# SoftCore_SA_P6.net
KiCad netlist of a schematic drawn in Altium Designer
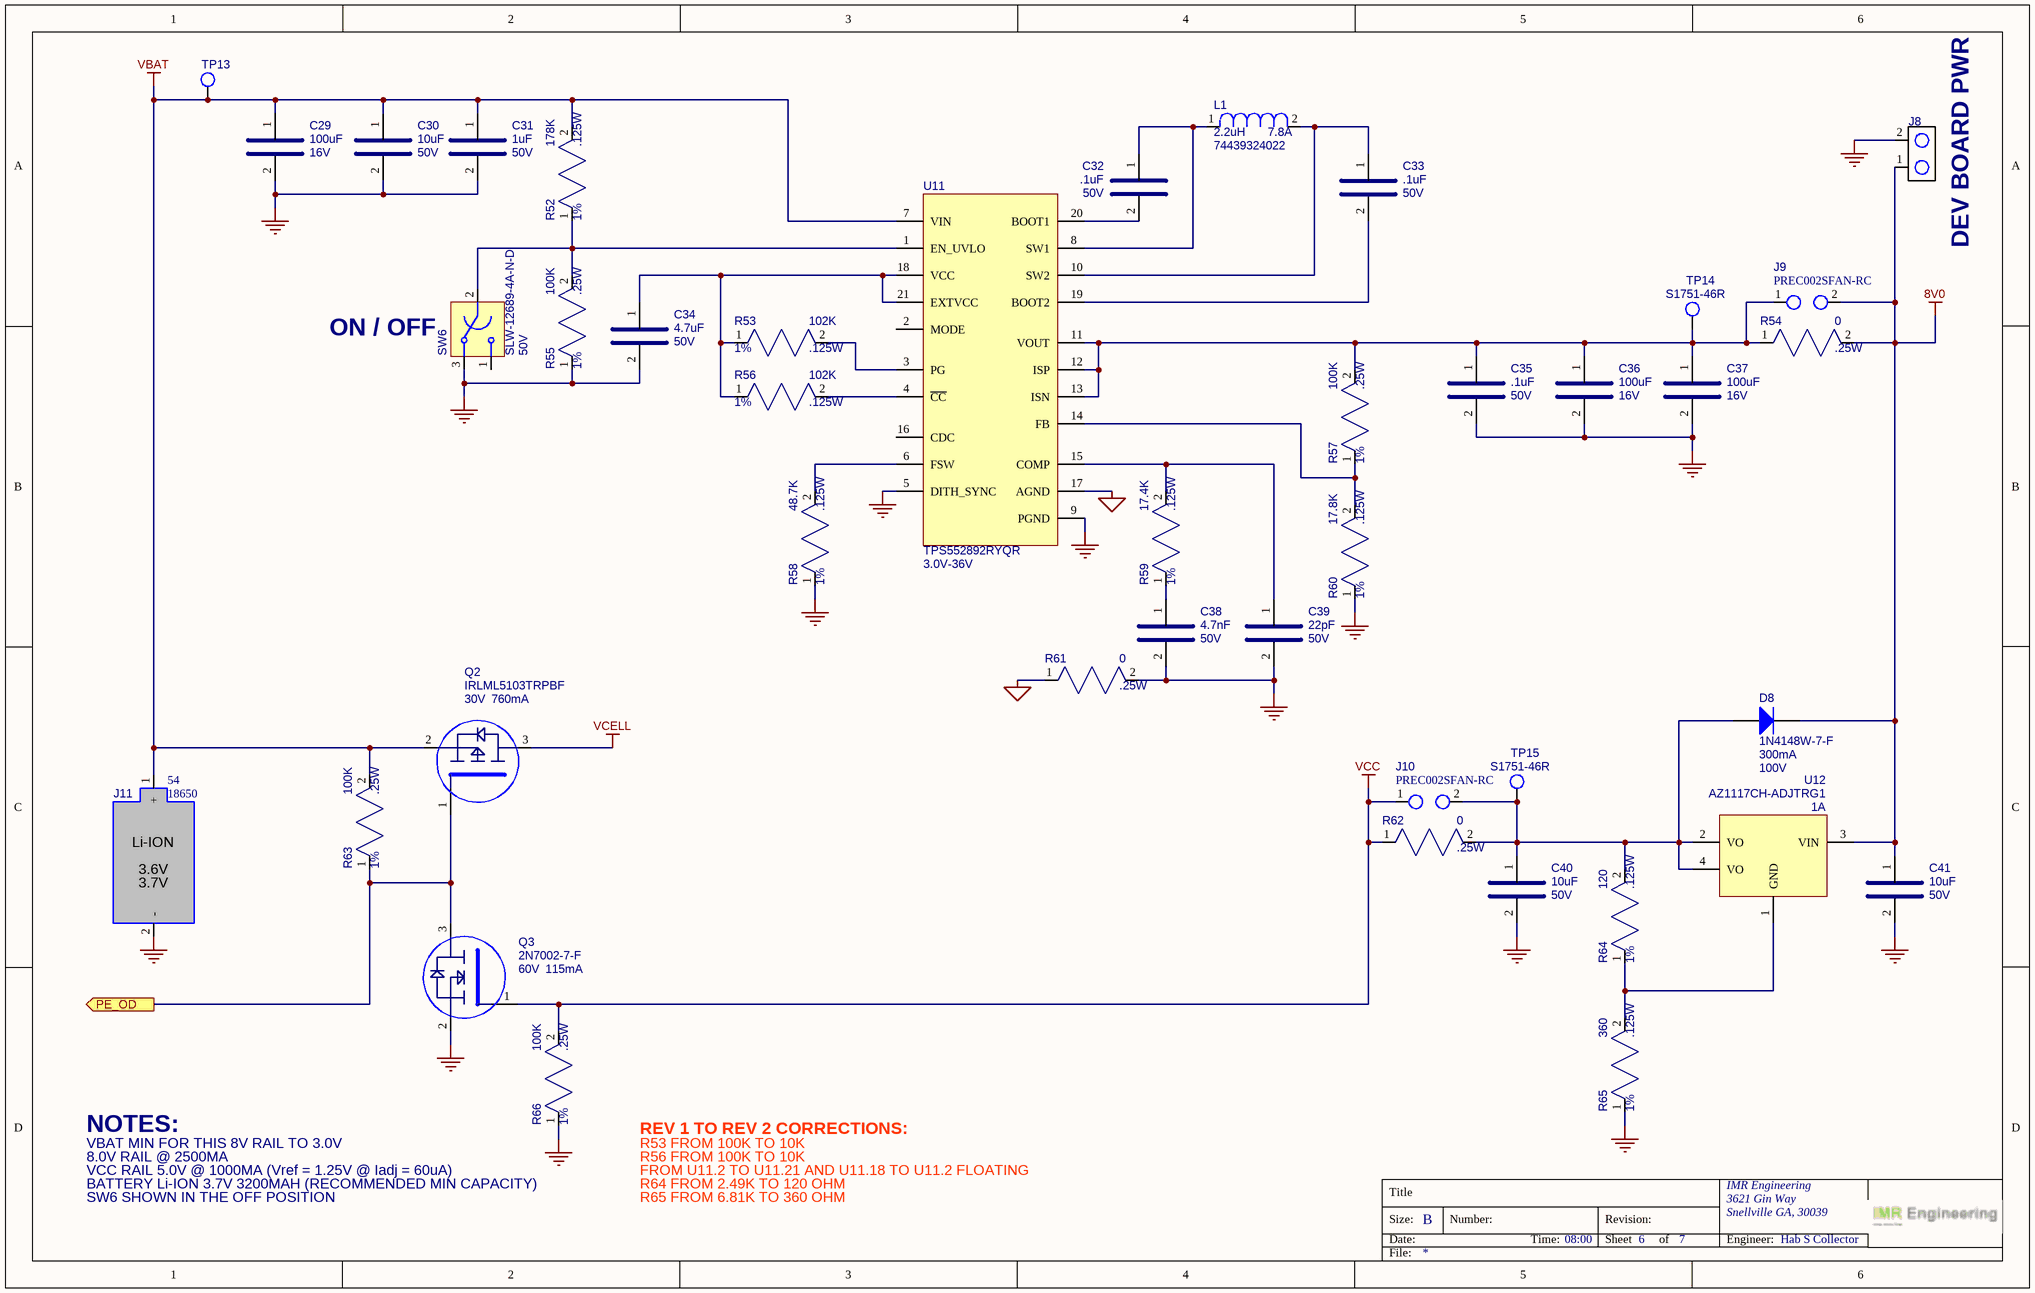
[diagram p0: SoftCore_SA_P6.SchDoc]

(export (version "E")
  (design (tool "Eeschema 10.0.6"))
  (components
    (comp (ref "C29")
      (value "100uF")
      (footprint "CAP_1210")
      (description "CAP CER 100UF 16V X7S SMD")
      (fields
        (field (name "MFG") "Taiyo Yuden")
        (field (name "VOLTAGE") "16V")
        (field (name "Comment") "EMK325ABJ107MM-P")
      )
      (libsource (lib "IMR_LIB_SCH_R2") (part "CAP_SMD_100UF_16V_SMD"))
    )
    (comp (ref "C30")
      (value "10uF")
      (footprint "CAP_0805")
      (description "CAP CER 10UF 50V X5R 0805")
      (fields
        (field (name "MFG") "Murata Electronics")
        (field (name "VOLTAGE") "50V")
        (field (name "Comment") "GRM21BR61H106KE43L")
      )
      (libsource (lib "IMR_LIB_SCH_R2") (part "CAP_SMD_10UF_50V_0805"))
    )
    (comp (ref "C31")
      (value "1uF")
      (footprint "CAP_0805")
      (description "CAP CER 1UF 50V X7R 0805")
      (fields
        (field (name "MFG") "KYOCERA AVX")
        (field (name "VOLTAGE") "50V")
        (field (name "Comment") "08055C105K4T2A")
      )
      (libsource (lib "IMR_LIB_SCH_R2") (part "CAP_SMD_1UF_50V_0805"))
    )
    (comp (ref "C32")
      (value ".1uF")
      (footprint "CAP_0805")
      (description "CAP CER 0.1UF 50V X7R 0805")
      (fields
        (field (name "MFG") "KYOCERA AVX")
        (field (name "VOLTAGE") "50V")
        (field (name "Comment") "KGM21NR71H104KT")
      )
      (libsource (lib "IMR_LIB_SCH_R2") (part "CAP_SMD_0.1UF_50V_0805"))
    )
    (comp (ref "C33")
      (value ".1uF")
      (footprint "CAP_0805")
      (description "CAP CER 0.1UF 50V X7R 0805")
      (fields
        (field (name "MFG") "KYOCERA AVX")
        (field (name "VOLTAGE") "50V")
        (field (name "Comment") "KGM21NR71H104KT")
      )
      (libsource (lib "IMR_LIB_SCH_R2") (part "CAP_SMD_0.1UF_50V_0805"))
    )
    (comp (ref "C34")
      (value "4.7uF")
      (footprint "CAP_0805")
      (description "CAP CER 4.7UF 50V X5R 0805")
      (fields
        (field (name "MFG") "Murata Electronics")
        (field (name "VOLTAGE") "50V")
        (field (name "Comment") "GRM21BR61H475KE51L")
      )
      (libsource (lib "IMR_LIB_SCH_R2") (part "CAP_SMD_4.7UF_50V_0805"))
    )
    (comp (ref "C35")
      (value ".1uF")
      (footprint "CAP_0805")
      (description "CAP CER 0.1UF 50V X7R 0805")
      (fields
        (field (name "MFG") "KYOCERA AVX")
        (field (name "VOLTAGE") "50V")
        (field (name "Comment") "KGM21NR71H104KT")
      )
      (libsource (lib "IMR_LIB_SCH_R2") (part "CAP_SMD_0.1UF_50V_0805"))
    )
    (comp (ref "C36")
      (value "100uF")
      (footprint "CAP_1210")
      (description "CAP CER 100UF 16V X7S SMD")
      (fields
        (field (name "MFG") "Taiyo Yuden")
        (field (name "VOLTAGE") "16V")
        (field (name "Comment") "EMK325ABJ107MM-P")
      )
      (libsource (lib "IMR_LIB_SCH_R2") (part "CAP_SMD_100UF_16V_SMD"))
    )
    (comp (ref "C37")
      (value "100uF")
      (footprint "CAP_1210")
      (description "CAP CER 100UF 16V X7S SMD")
      (fields
        (field (name "MFG") "Taiyo Yuden")
        (field (name "VOLTAGE") "16V")
        (field (name "Comment") "EMK325ABJ107MM-P")
      )
      (libsource (lib "IMR_LIB_SCH_R2") (part "CAP_SMD_100UF_16V_SMD"))
    )
    (comp (ref "C38")
      (value "4.7nF")
      (footprint "CAP_0805")
      (description "CAP CER 4.7NF 50V X7R 0805")
      (fields
        (field (name "MFG") "KEMET")
        (field (name "VOLTAGE") "50V")
        (field (name "Comment") "C0805C472K5RACAUTO")
      )
      (libsource (lib "IMR_LIB_SCH_R2") (part "CAP_SMD_4.7NF_50V_0805"))
    )
    (comp (ref "C39")
      (value "22pF")
      (footprint "CAP_0805")
      (description "CAP CER 22PF 50V X7R 0805")
      (fields
        (field (name "MFG") "KEMET")
        (field (name "VOLTAGE") "50V")
        (field (name "Comment") "C0805C220K5RACAUTO")
      )
      (libsource (lib "IMR_LIB_SCH_R2") (part "CAP_SMD_22PF_50V_0805"))
    )
    (comp (ref "C40")
      (value "10uF")
      (footprint "CAP_0805")
      (description "CAP CER 10UF 50V X5R 0805")
      (fields
        (field (name "MFG") "Murata Electronics")
        (field (name "VOLTAGE") "50V")
        (field (name "Comment") "GRM21BR61H106KE43L")
      )
      (libsource (lib "IMR_LIB_SCH_R2") (part "CAP_SMD_10UF_50V_0805"))
    )
    (comp (ref "C41")
      (value "10uF")
      (footprint "CAP_0805")
      (description "CAP CER 10UF 50V X5R 0805")
      (fields
        (field (name "MFG") "Murata Electronics")
        (field (name "VOLTAGE") "50V")
        (field (name "Comment") "GRM21BR61H106KE43L")
      )
      (libsource (lib "IMR_LIB_SCH_R2") (part "CAP_SMD_10UF_50V_0805"))
    )
    (comp (ref "D8")
      (value "100V")
      (footprint "SOD123")
      (description "RELAY REED SPDT 250MA 5V")
      (fields
        (field (name "MFG") "Diodes Inc")
        (field (name "MFG_PN") "1N4148W-7-F")
        (field (name "CURRENT") "300mA")
        (field (name "Comment") "1N4148W-7-F")
      )
      (libsource (lib "IMR_LIB_SCH_R2") (part "DIODE_1N4148W-7-F"))
    )
    (comp (ref "J8")
      (value "PREC002SFAN-RC")
      (footprint "HDR_1X2_100MILL")
      (description "CONN HEADER VERT 2POS 2.54MM")
      (fields (field (name "MFG") "Sullins Connector Solutions"))
      (libsource (lib "IMR_LIB_SCH_R2") (part "CONN_HEADER_2P_100MIL_VERT"))
    )
    (comp (ref "J9")
      (value "PREC002SFAN-RC")
      (footprint "HDR_1X2_100MILL")
      (description "CONN HEADER VERT 2POS 2.54MM")
      (fields (field (name "MFG") "Sullins Connector Solutions"))
      (libsource (lib "IMR_LIB_SCH_R2") (part "CONN_JUMPER_2P_100MIL_VERT"))
    )
    (comp (ref "J10")
      (value "PREC002SFAN-RC")
      (footprint "HDR_1X2_100MILL")
      (description "CONN HEADER VERT 2POS 2.54MM")
      (fields (field (name "MFG") "Sullins Connector Solutions"))
      (libsource (lib "IMR_LIB_SCH_R2") (part "CONN_JUMPER_2P_100MIL_VERT"))
    )
    (comp (ref "J11")
      (value "18650")
      (footprint "CONN_BATTERY_18650")
      (description "CONN HEADER VERT 2POS 2.54MM")
      (fields
        (field (name "MFG") "Keystone Electronics")
        (field (name "MFG_PN") "54")
        (field (name "Comment") "54")
      )
      (libsource (lib "IMR_LIB_SCH_R2") (part "CONN_BATT_18650"))
    )
    (comp (ref "L1")
      (value "2.2uH")
      (footprint "WE-XHMI_4030")
      (description "POWER INDUCTOR 4030; 2.2UH; 7.80")
      (fields
        (field (name "MFG") "Würth Elektronik")
        (field (name "TOLERANCE") "20%")
        (field (name "MFG_PN") "74439324022")
        (field (name "CURRENT") "7.8A")
      )
      (libsource (lib "IMR_LIB_SCH_R2") (part "INDUCTOR_74439324022"))
    )
    (comp (ref "Q2")
      (value "30V")
      (footprint "SOT-23")
      (description "MOSFET P-CH 30V 760MA SOT23")
      (fields
        (field (name "MFG") "Infineon Technologies")
        (field (name "MFG_PN") "IRLML5103TRPBF")
        (field (name "CURRENT") "760mA")
        (field (name "Comment") "IRLML5103TRPBF")
      )
      (libsource (lib "IMR_LIB_SCH_R2") (part "MOSFET_PCH_IRLML5103TRPBF"))
    )
    (comp (ref "Q3")
      (value "60V")
      (footprint "SOT-23")
      (description "MOSFET N-CH 60V 115MA SOT23-3")
      (fields
        (field (name "MFG") "Diodes Inc")
        (field (name "MFG_PN") "2N7002-7-F")
        (field (name "CURRENT") "115mA")
        (field (name "Comment") "2N7002-7-F")
      )
      (libsource (lib "IMR_LIB_SCH_R2") (part "MOSFET_NCH_2N7002-7-F"))
    )
    (comp (ref "R52")
      (value "178K")
      (footprint "RES_0805")
      (description "RES SMD 178K OHM 1% 1/8W 0805")
      (fields
        (field (name "MFG") "Yageo")
        (field (name "POWER") ".125W")
        (field (name "TOLERANCE") "1%")
        (field (name "Comment") "RC0805FR-07178KL")
      )
      (libsource (lib "IMR_LIB_SCH_R2") (part "RES_SMD_178K_0805_1/8W_1%"))
    )
    (comp (ref "R53")
      (value "102K")
      (footprint "RES_0805")
      (description "RES SMD 102K OHM 1% 1/8W 0805")
      (fields
        (field (name "MFG") "Yageo")
        (field (name "POWER") ".125W")
        (field (name "TOLERANCE") "1%")
        (field (name "Comment") "RC0805FR-07102KL")
      )
      (libsource (lib "IMR_LIB_SCH_R2") (part "RES_SMD_102K_0805_1/8W_1%"))
    )
    (comp (ref "R54")
      (value "0")
      (footprint "RES_0805")
      (description "RES SMD 0 OHM 1% 1/8W 0805")
      (fields (field (name "MFG") "Yageo") (field (name "TOLERANCE") "1%") (field (name "POWER") ".25W"))
      (libsource (lib "IMR_LIB_SCH_R2") (part "RES_SMD_0_0805_1/8W_1%"))
    )
    (comp (ref "R55")
      (value "100K")
      (footprint "RES_0805")
      (description "RES SMD 100K OHM 1% 1/4W 0805")
      (fields
        (field (name "MFG") "Yageo")
        (field (name "POWER") ".25W")
        (field (name "TOLERANCE") "1%")
        (field (name "Comment") "RC0805FR-07100KL")
      )
      (libsource (lib "IMR_LIB_SCH_R2") (part "RES_SMD_100K_0805_1/4W_1%"))
    )
    (comp (ref "R56")
      (value "102K")
      (footprint "RES_0805")
      (description "RES SMD 102K OHM 1% 1/8W 0805")
      (fields
        (field (name "MFG") "Yageo")
        (field (name "POWER") ".125W")
        (field (name "TOLERANCE") "1%")
        (field (name "Comment") "RC0805FR-07102KL")
      )
      (libsource (lib "IMR_LIB_SCH_R2") (part "RES_SMD_102K_0805_1/8W_1%"))
    )
    (comp (ref "R57")
      (value "100K")
      (footprint "RES_0805")
      (description "RES SMD 100K OHM 1% 1/4W 0805")
      (fields
        (field (name "MFG") "Yageo")
        (field (name "POWER") ".25W")
        (field (name "TOLERANCE") "1%")
        (field (name "Comment") "RC0805FR-07100KL")
      )
      (libsource (lib "IMR_LIB_SCH_R2") (part "RES_SMD_100K_0805_1/4W_1%"))
    )
    (comp (ref "R58")
      (value "48.7K")
      (footprint "RES_0805")
      (description "RES SMD 48.7K OHM 1% 1/8W 0805")
      (fields
        (field (name "MFG") "Yageo")
        (field (name "POWER") ".125W")
        (field (name "TOLERANCE") "1%")
        (field (name "Comment") "RC0805FR-0748K7L")
      )
      (libsource (lib "IMR_LIB_SCH_R2") (part "RES_SMD_48.7K_0805_1/8W_1%"))
    )
    (comp (ref "R59")
      (value "17.4K")
      (footprint "RES_0805")
      (description "RES SMD 17.4K OHM 1% 1/8W 0805")
      (fields
        (field (name "MFG") "Yageo")
        (field (name "POWER") ".125W")
        (field (name "TOLERANCE") "1%")
        (field (name "Comment") "RC0805FR-0717K4L")
      )
      (libsource (lib "IMR_LIB_SCH_R2") (part "RES_SMD_17.4K_0805_1/8W_1%"))
    )
    (comp (ref "R60")
      (value "17.8K")
      (footprint "RES_0805")
      (description "RES SMD 17.8K OHM 1% 1/8W 0805")
      (fields
        (field (name "MFG") "Yageo")
        (field (name "POWER") ".125W")
        (field (name "TOLERANCE") "1%")
        (field (name "Comment") "RC0805FR-0717K8L")
      )
      (libsource (lib "IMR_LIB_SCH_R2") (part "RES_SMD_17.8K_0805_1/8W_1%"))
    )
    (comp (ref "R61")
      (value "0")
      (footprint "RES_0805")
      (description "RES SMD 0 OHM 1% 1/8W 0805")
      (fields (field (name "MFG") "Yageo") (field (name "TOLERANCE") "1%") (field (name "POWER") ".25W"))
      (libsource (lib "IMR_LIB_SCH_R2") (part "RES_SMD_0_0805_1/8W_1%"))
    )
    (comp (ref "R62")
      (value "0")
      (footprint "RES_0805")
      (description "RES SMD 0 OHM 1% 1/8W 0805")
      (fields (field (name "MFG") "Yageo") (field (name "TOLERANCE") "1%") (field (name "POWER") ".25W"))
      (libsource (lib "IMR_LIB_SCH_R2") (part "RES_SMD_0_0805_1/8W_1%"))
    )
    (comp (ref "R63")
      (value "100K")
      (footprint "RES_0805")
      (description "RES SMD 100K OHM 1% 1/4W 0805")
      (fields
        (field (name "MFG") "Yageo")
        (field (name "POWER") ".25W")
        (field (name "TOLERANCE") "1%")
        (field (name "Comment") "RC0805FR-07100KL")
      )
      (libsource (lib "IMR_LIB_SCH_R2") (part "RES_SMD_100K_0805_1/4W_1%"))
    )
    (comp (ref "R64")
      (value "120")
      (footprint "RES_0805")
      (description "RES SMD 2.49K OHM 1% 1/8W 0805")
      (fields
        (field (name "MFG") "Yageo")
        (field (name "POWER") ".125W")
        (field (name "TOLERANCE") "1%")
        (field (name "Comment") "RC0805FR-132K49L")
      )
      (libsource (lib "IMR_LIB_SCH_R2") (part "RES_SMD_2.49K_0805_1/8W_1%"))
    )
    (comp (ref "R65")
      (value "360")
      (footprint "RES_0805")
      (description "RES SMD 6.81K OHM 1% 1/8W 0805")
      (fields
        (field (name "MFG") "Yageo")
        (field (name "POWER") ".125W")
        (field (name "TOLERANCE") "1%")
        (field (name "Comment") "RC0805FR-076K81L")
      )
      (libsource (lib "IMR_LIB_SCH_R2") (part "RES_SMD_6.81K_0805_1/8W_1%"))
    )
    (comp (ref "R66")
      (value "100K")
      (footprint "RES_0805")
      (description "RES SMD 100K OHM 1% 1/4W 0805")
      (fields
        (field (name "MFG") "Yageo")
        (field (name "POWER") ".25W")
        (field (name "TOLERANCE") "1%")
        (field (name "Comment") "RC0805FR-07100KL")
      )
      (libsource (lib "IMR_LIB_SCH_R2") (part "RES_SMD_100K_0805_1/4W_1%"))
    )
    (comp (ref "SW6")
      (value "50V")
      (footprint "SLW126894AND")
      (description "SWITCH SLIDE SPDT 300MA 50V")
      (fields
        (field (name "MFG") "Same Sky")
        (field (name "MFG_PN") "SLW-12689-4A-N-D")
        (field (name "Comment") "SLW-12689-4A-N-D")
      )
      (libsource (lib "IMR_LIB_SCH_R2") (part "SWITCH_SLW-12689-4A-N-D"))
    )
    (comp (ref "TP13")
      (value "~")
      (footprint "TEST_POINT_20MIL_TH")
      (description "TEST POINT TH 20MIL HOLE")
      (libsource (lib "IMR_LIB_SCH_R2") (part "CONN_TEST_POINT_TH_PAD_20MIL"))
    )
    (comp (ref "TP14")
      (value "S1751-46R")
      (footprint "HARWIN_S1751")
      (description "PCB TEST POINT CONNECT")
      (fields (field (name "MFG") "Harwin Inc") (field (name "MFG_PN") "S1751-46R"))
      (libsource (lib "IMR_LIB_SCH_R2") (part "CONN_TEST_POINT_S1751-46R"))
    )
    (comp (ref "TP15")
      (value "S1751-46R")
      (footprint "HARWIN_S1751")
      (description "PCB TEST POINT CONNECT")
      (fields (field (name "MFG") "Harwin Inc") (field (name "MFG_PN") "S1751-46R"))
      (libsource (lib "IMR_LIB_SCH_R2") (part "CONN_TEST_POINT_S1751-46R"))
    )
    (comp (ref "U11")
      (value "3.0V-36V")
      (footprint "CONV_TPS552892RYQR")
      (description "IC REG BUCK ADJ 1A 16HTSSOP")
      (fields
        (field (name "MFG") "Texas Instruments")
        (field (name "MFG_PN") "TPS552892RYQR")
        (field (name "Comment") "TPS552892RYQR")
      )
      (libsource (lib "IMR_LIB_SCH_R2") (part "IC_SMPS_TPS552892RYQR"))
    )
    (comp (ref "U12")
      (value "AZ1117CH-ADJTRG1")
      (footprint "SOT223")
      (description "IC REG BUCK ADJ 2A SOT23")
      (fields
        (field (name "MFG") "Diodes Incorporated")
        (field (name "CURRENT") "1A")
        (field (name "MFG_PN") "AZ1117CH-ADJTRG1")
      )
      (libsource (lib "IMR_LIB_SCH_R2") (part "IC_REG_AZ1117CH-ADJTRG1"))
    )
  )
  (nets
    (net (code "1") (name "/PE_OD") (class "Default")
      (node (ref "Q2") (pin "1") (pinfunction "G_1") (pintype "passive"))
      (node (ref "Q3") (pin "3") (pinfunction "C_3") (pintype "passive"))
      (node (ref "R63") (pin "1") (pinfunction "1_1") (pintype "passive"))
    )
    (net (code "2") (name "8V0") (class "Default")
      (node (ref "C41") (pin "1") (pinfunction "1_1") (pintype "passive"))
      (node (ref "D8") (pin "2") (pinfunction "K_2") (pintype "passive"))
      (node (ref "J8") (pin "1") (pintype "passive"))
      (node (ref "J9") (pin "2") (pintype "passive"))
      (node (ref "R54") (pin "2") (pinfunction "2_2") (pintype "passive"))
      (node (ref "U12") (pin "3") (pinfunction "VIN_3") (pintype "passive"))
    )
    (net (code "3") (name "AGND") (class "Default")
      (node (ref "R61") (pin "1") (pinfunction "1_1") (pintype "passive"))
      (node (ref "U11") (pin "17") (pinfunction "AGND_17") (pintype "passive"))
    )
    (net (code "4") (name "GND") (class "Default")
      (node (ref "C29") (pin "2") (pinfunction "2_2") (pintype "passive"))
      (node (ref "C30") (pin "2") (pinfunction "2_2") (pintype "passive"))
      (node (ref "C31") (pin "2") (pinfunction "2_2") (pintype "passive"))
      (node (ref "C34") (pin "2") (pinfunction "2_2") (pintype "passive"))
      (node (ref "C35") (pin "2") (pinfunction "2_2") (pintype "passive"))
      (node (ref "C36") (pin "2") (pinfunction "2_2") (pintype "passive"))
      (node (ref "C37") (pin "2") (pinfunction "2_2") (pintype "passive"))
      (node (ref "C38") (pin "2") (pinfunction "2_2") (pintype "passive"))
      (node (ref "C39") (pin "2") (pinfunction "2_2") (pintype "passive"))
      (node (ref "C40") (pin "2") (pinfunction "2_2") (pintype "passive"))
      (node (ref "C41") (pin "2") (pinfunction "2_2") (pintype "passive"))
      (node (ref "J11") (pin "2") (pinfunction "-_2") (pintype "passive"))
      (node (ref "J8") (pin "2") (pintype "passive"))
      (node (ref "Q3") (pin "2") (pinfunction "E_2") (pintype "passive"))
      (node (ref "R55") (pin "1") (pinfunction "1_1") (pintype "passive"))
      (node (ref "R58") (pin "1") (pinfunction "1_1") (pintype "passive"))
      (node (ref "R60") (pin "1") (pinfunction "1_1") (pintype "passive"))
      (node (ref "R61") (pin "2") (pinfunction "2_2") (pintype "passive"))
      (node (ref "R65") (pin "1") (pinfunction "1_1") (pintype "passive"))
      (node (ref "R66") (pin "1") (pinfunction "1_1") (pintype "passive"))
      (node (ref "SW6") (pin "3") (pintype "passive"))
      (node (ref "U11") (pin "5") (pinfunction "DITH_SYNC_5") (pintype "passive"))
      (node (ref "U11") (pin "9") (pinfunction "PGND_9") (pintype "passive"))
    )
    (net (code "5") (name "Net-(C38-Pad1)") (class "Default")
      (node (ref "C38") (pin "1") (pinfunction "1_1") (pintype "passive"))
      (node (ref "R59") (pin "1") (pinfunction "1_1") (pintype "passive"))
    )
    (net (code "6") (name "Net-(D8-A)") (class "Default")
      (node (ref "C40") (pin "1") (pinfunction "1_1") (pintype "passive"))
      (node (ref "D8") (pin "1") (pinfunction "A_1") (pintype "passive"))
      (node (ref "J10") (pin "2") (pintype "passive"))
      (node (ref "R62") (pin "2") (pinfunction "2_2") (pintype "passive"))
      (node (ref "R64") (pin "2") (pinfunction "2_2") (pintype "passive"))
      (node (ref "TP15") (pin "1") (pintype "passive"))
      (node (ref "U12") (pin "2") (pinfunction "VO_2") (pintype "passive"))
      (node (ref "U12") (pin "4") (pinfunction "VO_4") (pintype "passive"))
    )
    (net (code "7") (name "Net-(U11-BOOT1)") (class "Default")
      (node (ref "C32") (pin "2") (pinfunction "2_2") (pintype "passive"))
      (node (ref "U11") (pin "20") (pinfunction "BOOT1_20") (pintype "passive"))
    )
    (net (code "8") (name "Net-(U11-BOOT2)") (class "Default")
      (node (ref "C33") (pin "2") (pinfunction "2_2") (pintype "passive"))
      (node (ref "U11") (pin "19") (pinfunction "BOOT2_19") (pintype "passive"))
    )
    (net (code "9") (name "Net-(U11-COMP)") (class "Default")
      (node (ref "C39") (pin "1") (pinfunction "1_1") (pintype "passive"))
      (node (ref "R59") (pin "2") (pinfunction "2_2") (pintype "passive"))
      (node (ref "U11") (pin "15") (pinfunction "COMP_15") (pintype "passive"))
    )
    (net (code "10") (name "Net-(U11-EN_UVLO)") (class "Default")
      (node (ref "R52") (pin "1") (pinfunction "1_1") (pintype "passive"))
      (node (ref "R55") (pin "2") (pinfunction "2_2") (pintype "passive"))
      (node (ref "SW6") (pin "2") (pintype "passive"))
      (node (ref "U11") (pin "1") (pinfunction "EN_UVLO_1") (pintype "passive"))
    )
    (net (code "11") (name "Net-(U11-EXTVCC)") (class "Default")
      (node (ref "C34") (pin "1") (pinfunction "1_1") (pintype "passive"))
      (node (ref "R53") (pin "1") (pinfunction "1_1") (pintype "passive"))
      (node (ref "R56") (pin "1") (pinfunction "1_1") (pintype "passive"))
      (node (ref "U11") (pin "18") (pinfunction "VCC_18") (pintype "passive"))
      (node (ref "U11") (pin "21") (pinfunction "EXTVCC_21") (pintype "passive"))
    )
    (net (code "12") (name "Net-(U11-FB)") (class "Default")
      (node (ref "R57") (pin "1") (pinfunction "1_1") (pintype "passive"))
      (node (ref "R60") (pin "2") (pinfunction "2_2") (pintype "passive"))
      (node (ref "U11") (pin "14") (pinfunction "FB_14") (pintype "passive"))
    )
    (net (code "13") (name "Net-(U11-FSW)") (class "Default")
      (node (ref "R58") (pin "2") (pinfunction "2_2") (pintype "passive"))
      (node (ref "U11") (pin "6") (pinfunction "FSW_6") (pintype "passive"))
    )
    (net (code "14") (name "Net-(U11-ISN)") (class "Default")
      (node (ref "C35") (pin "1") (pinfunction "1_1") (pintype "passive"))
      (node (ref "C36") (pin "1") (pinfunction "1_1") (pintype "passive"))
      (node (ref "C37") (pin "1") (pinfunction "1_1") (pintype "passive"))
      (node (ref "J9") (pin "1") (pintype "passive"))
      (node (ref "R54") (pin "1") (pinfunction "1_1") (pintype "passive"))
      (node (ref "R57") (pin "2") (pinfunction "2_2") (pintype "passive"))
      (node (ref "TP14") (pin "1") (pintype "passive"))
      (node (ref "U11") (pin "11") (pinfunction "VOUT_11") (pintype "passive"))
      (node (ref "U11") (pin "12") (pinfunction "ISP_12") (pintype "passive"))
      (node (ref "U11") (pin "13") (pinfunction "ISN_13") (pintype "passive"))
    )
    (net (code "15") (name "Net-(U11-PG)") (class "Default")
      (node (ref "R53") (pin "2") (pinfunction "2_2") (pintype "passive"))
      (node (ref "U11") (pin "3") (pinfunction "PG_3") (pintype "passive"))
    )
    (net (code "16") (name "Net-(U11-SW1)") (class "Default")
      (node (ref "C32") (pin "1") (pinfunction "1_1") (pintype "passive"))
      (node (ref "L1") (pin "1") (pinfunction "1_1") (pintype "passive"))
      (node (ref "U11") (pin "8") (pinfunction "SW1_8") (pintype "passive"))
    )
    (net (code "17") (name "Net-(U11-SW2)") (class "Default")
      (node (ref "C33") (pin "1") (pinfunction "1_1") (pintype "passive"))
      (node (ref "L1") (pin "2") (pinfunction "2_2") (pintype "passive"))
      (node (ref "U11") (pin "10") (pinfunction "SW2_10") (pintype "passive"))
    )
    (net (code "18") (name "Net-(U11-~{CC})") (class "Default")
      (node (ref "R56") (pin "2") (pinfunction "2_2") (pintype "passive"))
      (node (ref "U11") (pin "4") (pinfunction "~{CC}_4") (pintype "passive"))
    )
    (net (code "19") (name "Net-(U12-GND)") (class "Default")
      (node (ref "R64") (pin "1") (pinfunction "1_1") (pintype "passive"))
      (node (ref "R65") (pin "2") (pinfunction "2_2") (pintype "passive"))
      (node (ref "U12") (pin "1") (pinfunction "GND_1") (pintype "passive"))
    )
    (net (code "20") (name "VBAT") (class "Default")
      (node (ref "C29") (pin "1") (pinfunction "1_1") (pintype "passive"))
      (node (ref "C30") (pin "1") (pinfunction "1_1") (pintype "passive"))
      (node (ref "C31") (pin "1") (pinfunction "1_1") (pintype "passive"))
      (node (ref "J11") (pin "1") (pinfunction "+_1") (pintype "passive"))
      (node (ref "Q2") (pin "2") (pinfunction "S_2") (pintype "passive"))
      (node (ref "R52") (pin "2") (pinfunction "2_2") (pintype "passive"))
      (node (ref "R63") (pin "2") (pinfunction "2_2") (pintype "passive"))
      (node (ref "TP13") (pin "1") (pintype "passive"))
      (node (ref "U11") (pin "7") (pinfunction "VIN_7") (pintype "passive"))
    )
    (net (code "21") (name "VCC") (class "Default")
      (node (ref "J10") (pin "1") (pintype "passive"))
      (node (ref "Q3") (pin "1") (pinfunction "B_1") (pintype "passive"))
      (node (ref "R62") (pin "1") (pinfunction "1_1") (pintype "passive"))
      (node (ref "R66") (pin "2") (pinfunction "2_2") (pintype "passive"))
    )
    (net (code "22") (name "VCELL") (class "Default")
      (node (ref "Q2") (pin "3") (pinfunction "D_3") (pintype "passive"))
    )
    (net (code "23") (name "unconnected-(SW6-Pad1)") (class "Default")
      (node (ref "SW6") (pin "1") (pintype "passive"))
    )
    (net (code "24") (name "unconnected-(U11-CDC-Pad16)") (class "Default")
      (node (ref "U11") (pin "16") (pinfunction "CDC_16") (pintype "passive"))
    )
    (net (code "25") (name "unconnected-(U11-MODE-Pad2)") (class "Default")
      (node (ref "U11") (pin "2") (pinfunction "MODE_2") (pintype "passive"))
    )
  )
)
